# ProPrj_TK021F2699-RGB___24____2024-11-26.net
KiCad netlist of a schematic drawn in EasyEDA Pro
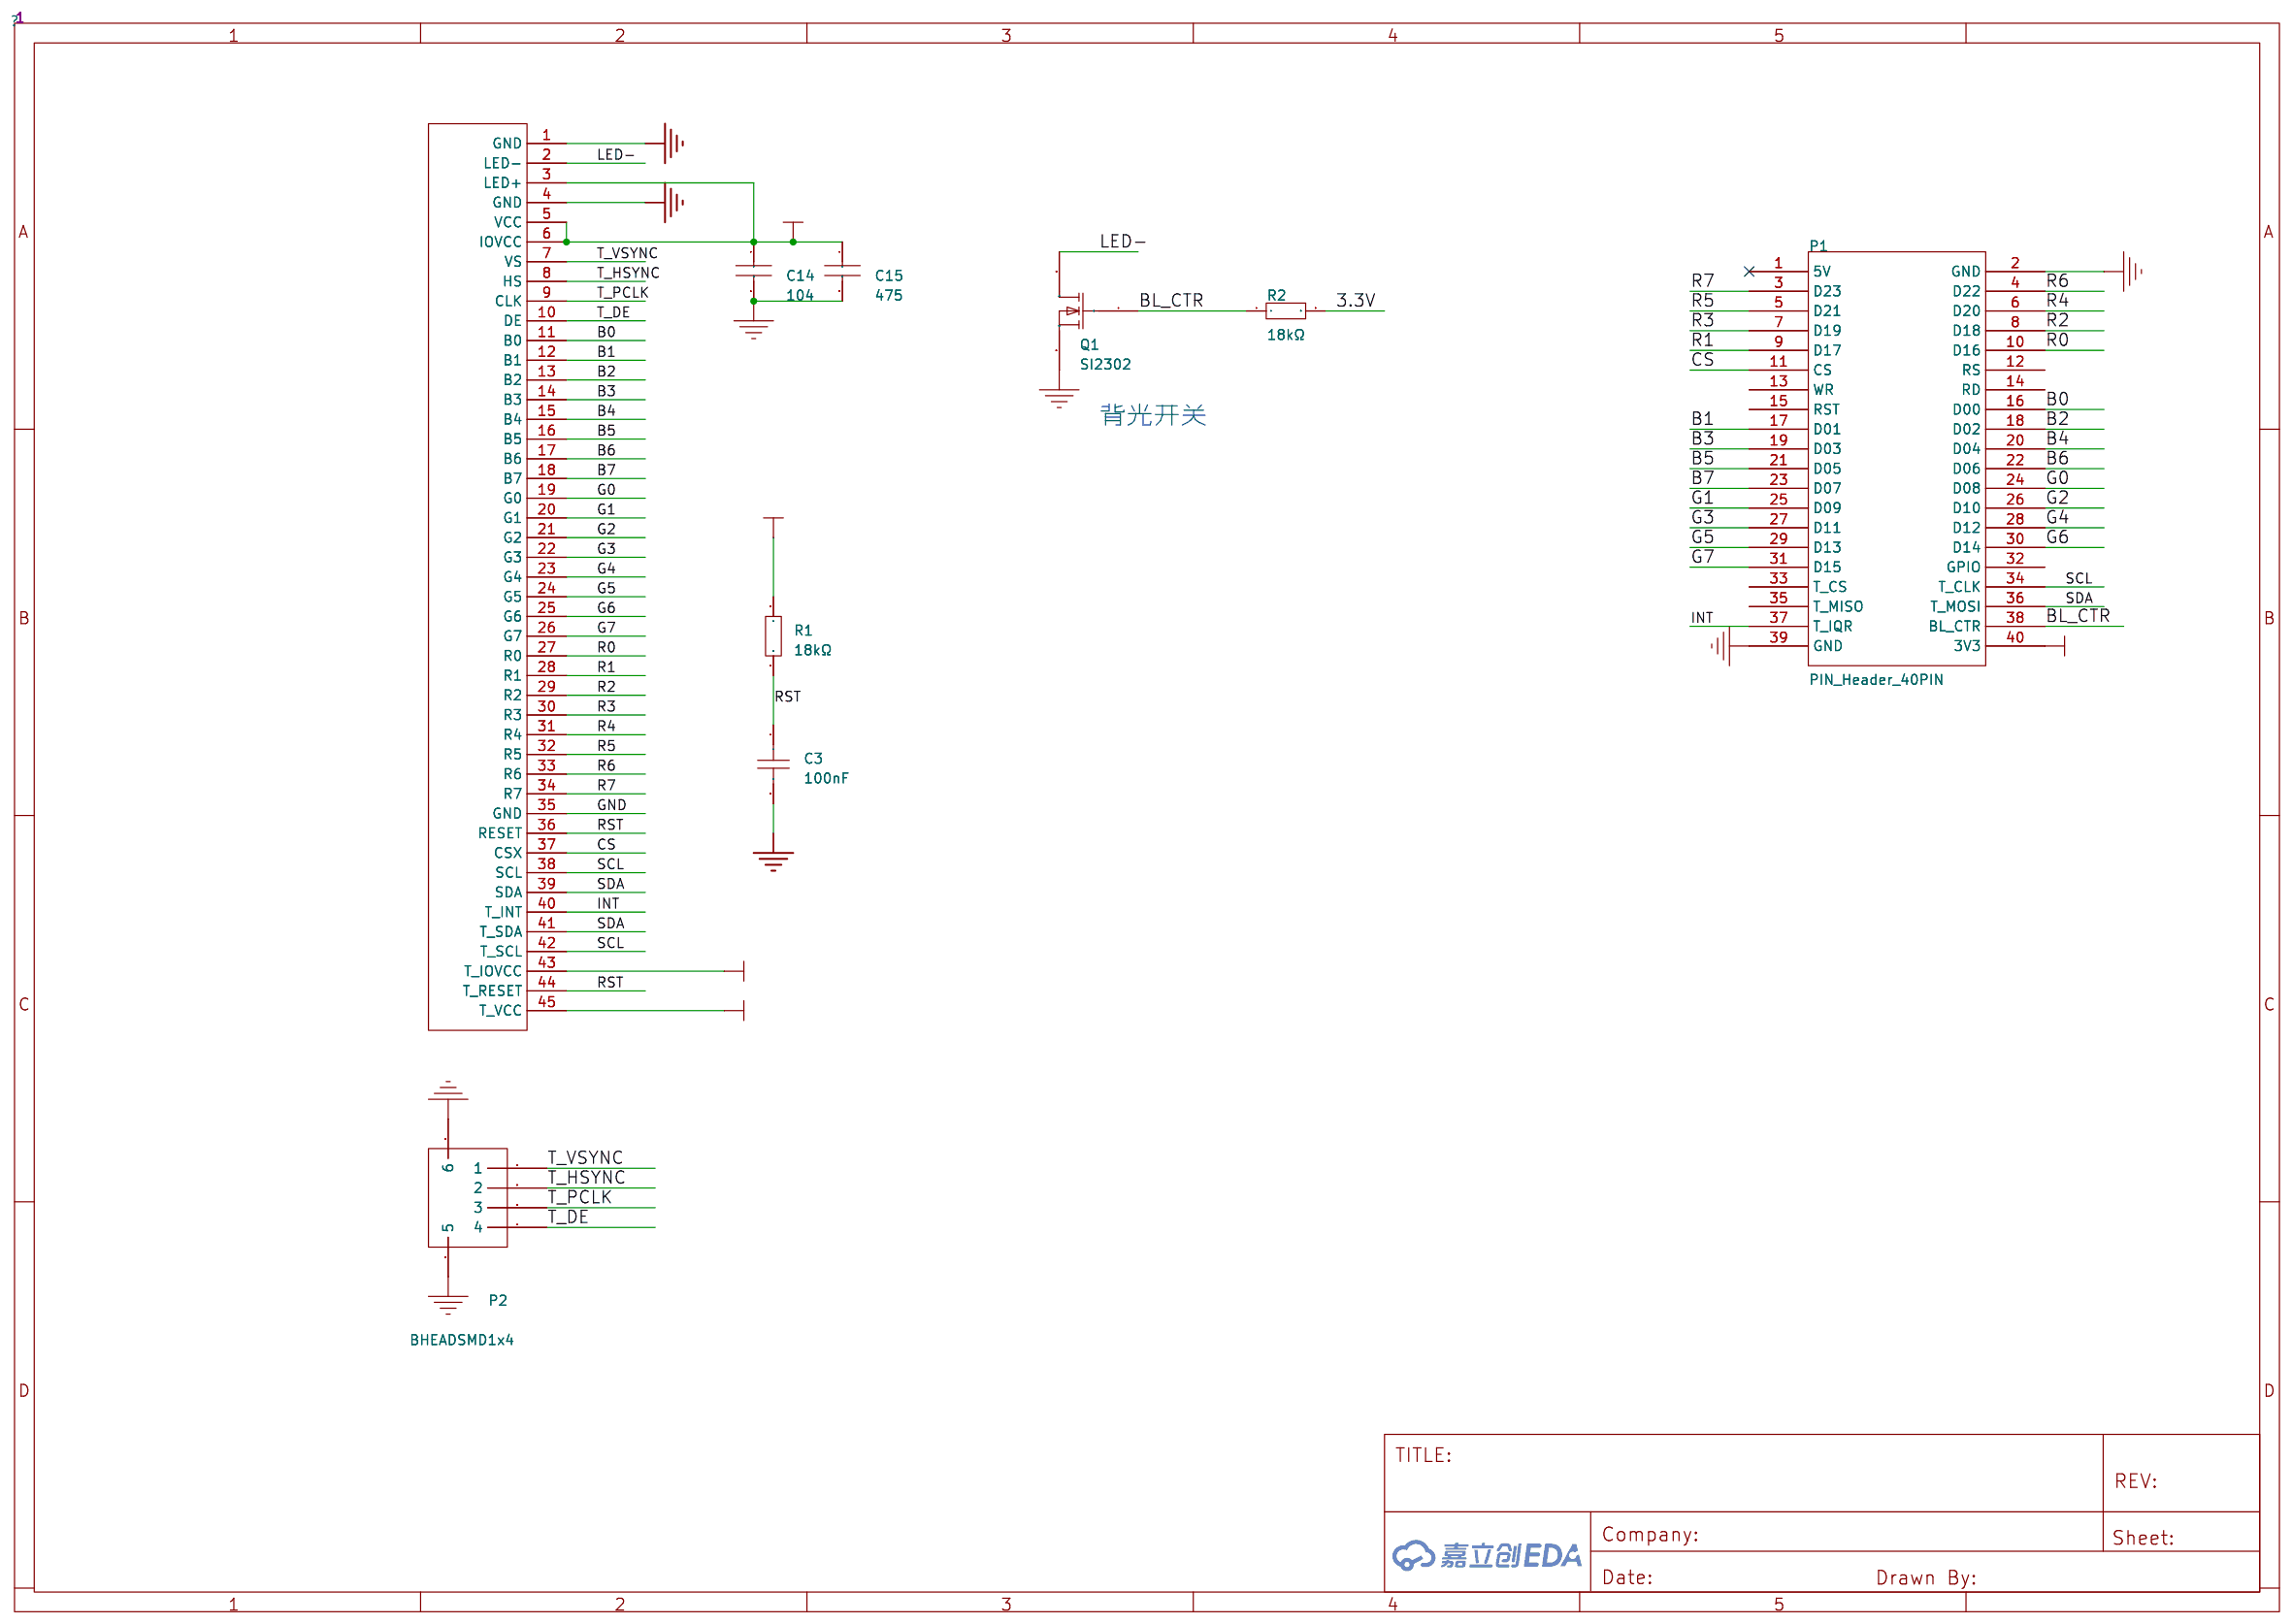
[diagram p0: schematic sheet]

(export (version "E")
  (design (tool "Eeschema 10.0.6"))
  (components
    (comp (ref "C3")
      (value "100nF")
      (footprint "easyedapro:C0603")
      (description "容值:100nF;精度:±10%;额定电压:50V;材质(温度系数):X7R;")
      (fields
        (field (name "Manufacturer Part") "CC0603KRX7R9BB104")
        (field (name "Manufacturer") "YAGEO(国巨)")
      )
      (libsource (lib "easyedapro") (part "CC0603KRX7R9BB104_1"))
    )
    (comp (ref "C14")
      (value "104")
      (footprint "easyedapro:C0603-1")
      (libsource (lib "easyedapro") (part "cap"))
    )
    (comp (ref "C15")
      (value "475")
      (footprint "easyedapro:C0603-1")
      (libsource (lib "easyedapro") (part "cap"))
    )
    (comp (ref "P1")
      (value "PIN_Header_40PIN")
      (footprint "easyedapro:P_Head_2x20")
      (libsource (lib "easyedapro") (part "PIN_Header_40PIN"))
    )
    (comp (ref "P2")
      (value "BHEADSMD1x4")
      (footprint "easyedapro:BHEADSMD1x4")
      (libsource (lib "easyedapro") (part "BHEADSMD1x4"))
    )
    (comp (ref "Q1")
      (value "SI2302")
      (footprint "easyedapro:SOT23A")
      (libsource (lib "easyedapro") (part "MOSFET-N"))
    )
    (comp (ref "R1")
      (value "18kΩ")
      (footprint "easyedapro:R0603")
      (description "电阻类型:厚膜电阻;阻值:18kΩ;精度:±1%;功率:100mW;最大工作电压:75V;温度系数:±100ppm/°C;")
      (fields
        (field (name "Manufacturer Part") "0603WAF1802T5E")
        (field (name "Manufacturer") "UNI-ROYAL(厚声)")
      )
      (libsource (lib "easyedapro") (part "0603WAF1802T5E_1"))
    )
    (comp (ref "R2")
      (value "18kΩ")
      (footprint "easyedapro:R0603")
      (description "电阻类型:厚膜电阻;阻值:18kΩ;精度:±1%;功率:100mW;最大工作电压:75V;温度系数:±100ppm/°C;")
      (fields
        (field (name "Manufacturer Part") "0603WAF1802T5E")
        (field (name "Manufacturer") "UNI-ROYAL(厚声)")
      )
      (libsource (lib "easyedapro") (part "0603WAF1802T5E_1"))
    )
    (comp (ref "U1")
      (value "~")
      (footprint "easyedapro:TK-45P")
      (libsource (lib "easyedapro") (part "TK021F2699-24"))
    )
  )
  (nets
    (net (code "1") (name "/B0") (class "Default")
      (node (ref "P1") (pin "16") (pinfunction "D00_16") (pintype "unspecified"))
      (node (ref "U1") (pin "11") (pinfunction "B0_11") (pintype "input"))
    )
    (net (code "2") (name "/B1") (class "Default")
      (node (ref "P1") (pin "17") (pinfunction "D01_17") (pintype "unspecified"))
      (node (ref "U1") (pin "12") (pinfunction "B1_12") (pintype "input"))
    )
    (net (code "3") (name "/B2") (class "Default")
      (node (ref "P1") (pin "18") (pinfunction "D02_18") (pintype "unspecified"))
      (node (ref "U1") (pin "13") (pinfunction "B2_13") (pintype "input"))
    )
    (net (code "4") (name "/B3") (class "Default")
      (node (ref "P1") (pin "19") (pinfunction "D03_19") (pintype "unspecified"))
      (node (ref "U1") (pin "14") (pinfunction "B3_14") (pintype "input"))
    )
    (net (code "5") (name "/B4") (class "Default")
      (node (ref "P1") (pin "20") (pinfunction "D04_20") (pintype "unspecified"))
      (node (ref "U1") (pin "15") (pinfunction "B4_15") (pintype "input"))
    )
    (net (code "6") (name "/B5") (class "Default")
      (node (ref "P1") (pin "21") (pinfunction "D05_21") (pintype "unspecified"))
      (node (ref "U1") (pin "16") (pinfunction "B5_16") (pintype "input"))
    )
    (net (code "7") (name "/B6") (class "Default")
      (node (ref "P1") (pin "22") (pinfunction "D06_22") (pintype "unspecified"))
      (node (ref "U1") (pin "17") (pinfunction "B6_17") (pintype "input"))
    )
    (net (code "8") (name "/B7") (class "Default")
      (node (ref "P1") (pin "23") (pinfunction "D07_23") (pintype "unspecified"))
      (node (ref "U1") (pin "18") (pinfunction "B7_18") (pintype "input"))
    )
    (net (code "9") (name "/BL_CTR") (class "Default")
      (node (ref "P1") (pin "38") (pinfunction "BL_CTR_38") (pintype "unspecified"))
      (node (ref "Q1") (pin "1") (pinfunction "G_1") (pintype "unspecified"))
      (node (ref "R2") (pin "1") (pinfunction "1_1") (pintype "input"))
    )
    (net (code "10") (name "/CS") (class "Default")
      (node (ref "P1") (pin "11") (pinfunction "CS_11") (pintype "unspecified"))
      (node (ref "U1") (pin "37") (pinfunction "CSX_37") (pintype "input"))
    )
    (net (code "11") (name "/G0") (class "Default")
      (node (ref "P1") (pin "24") (pinfunction "D08_24") (pintype "unspecified"))
      (node (ref "U1") (pin "19") (pinfunction "G0_19") (pintype "input"))
    )
    (net (code "12") (name "/G1") (class "Default")
      (node (ref "P1") (pin "25") (pinfunction "D09_25") (pintype "unspecified"))
      (node (ref "U1") (pin "20") (pinfunction "G1_20") (pintype "input"))
    )
    (net (code "13") (name "/G2") (class "Default")
      (node (ref "P1") (pin "26") (pinfunction "D10_26") (pintype "unspecified"))
      (node (ref "U1") (pin "21") (pinfunction "G2_21") (pintype "input"))
    )
    (net (code "14") (name "/G3") (class "Default")
      (node (ref "P1") (pin "27") (pinfunction "D11_27") (pintype "unspecified"))
      (node (ref "U1") (pin "22") (pinfunction "G3_22") (pintype "input"))
    )
    (net (code "15") (name "/G4") (class "Default")
      (node (ref "P1") (pin "28") (pinfunction "D12_28") (pintype "unspecified"))
      (node (ref "U1") (pin "23") (pinfunction "G4_23") (pintype "input"))
    )
    (net (code "16") (name "/G5") (class "Default")
      (node (ref "P1") (pin "29") (pinfunction "D13_29") (pintype "unspecified"))
      (node (ref "U1") (pin "24") (pinfunction "G5_24") (pintype "input"))
    )
    (net (code "17") (name "/G6") (class "Default")
      (node (ref "P1") (pin "30") (pinfunction "D14_30") (pintype "unspecified"))
      (node (ref "U1") (pin "25") (pinfunction "G6_25") (pintype "input"))
    )
    (net (code "18") (name "/G7") (class "Default")
      (node (ref "P1") (pin "31") (pinfunction "D15_31") (pintype "unspecified"))
      (node (ref "U1") (pin "26") (pinfunction "G7_26") (pintype "input"))
    )
    (net (code "19") (name "/INT") (class "Default")
      (node (ref "P1") (pin "37") (pinfunction "T_IQR_37") (pintype "unspecified"))
      (node (ref "U1") (pin "40") (pinfunction "T_INT_40") (pintype "input"))
    )
    (net (code "20") (name "/LED-") (class "Default")
      (node (ref "Q1") (pin "3") (pinfunction "D_3") (pintype "unspecified"))
      (node (ref "U1") (pin "2") (pinfunction "LED-_2") (pintype "input"))
    )
    (net (code "21") (name "/R0") (class "Default")
      (node (ref "P1") (pin "10") (pinfunction "D16_10") (pintype "unspecified"))
      (node (ref "U1") (pin "27") (pinfunction "R0_27") (pintype "input"))
    )
    (net (code "22") (name "/R1") (class "Default")
      (node (ref "P1") (pin "9") (pinfunction "D17_9") (pintype "unspecified"))
      (node (ref "U1") (pin "28") (pinfunction "R1_28") (pintype "input"))
    )
    (net (code "23") (name "/R2") (class "Default")
      (node (ref "P1") (pin "8") (pinfunction "D18_8") (pintype "unspecified"))
      (node (ref "U1") (pin "29") (pinfunction "R2_29") (pintype "input"))
    )
    (net (code "24") (name "/R3") (class "Default")
      (node (ref "P1") (pin "7") (pinfunction "D19_7") (pintype "unspecified"))
      (node (ref "U1") (pin "30") (pinfunction "R3_30") (pintype "input"))
    )
    (net (code "25") (name "/R4") (class "Default")
      (node (ref "P1") (pin "6") (pinfunction "D20_6") (pintype "unspecified"))
      (node (ref "U1") (pin "31") (pinfunction "R4_31") (pintype "input"))
    )
    (net (code "26") (name "/R5") (class "Default")
      (node (ref "P1") (pin "5") (pinfunction "D21_5") (pintype "unspecified"))
      (node (ref "U1") (pin "32") (pinfunction "R5_32") (pintype "input"))
    )
    (net (code "27") (name "/R6") (class "Default")
      (node (ref "P1") (pin "4") (pinfunction "D22_4") (pintype "unspecified"))
      (node (ref "U1") (pin "33") (pinfunction "R6_33") (pintype "input"))
    )
    (net (code "28") (name "/R7") (class "Default")
      (node (ref "P1") (pin "3") (pinfunction "D23_3") (pintype "unspecified"))
      (node (ref "U1") (pin "34") (pinfunction "R7_34") (pintype "input"))
    )
    (net (code "29") (name "/RST") (class "Default")
      (node (ref "C3") (pin "1") (pinfunction "1_1") (pintype "unspecified"))
      (node (ref "R1") (pin "1") (pinfunction "1_1") (pintype "input"))
      (node (ref "U1") (pin "36") (pinfunction "RESET_36") (pintype "input"))
      (node (ref "U1") (pin "44") (pinfunction "T_RESET_44") (pintype "input"))
    )
    (net (code "30") (name "/SCL") (class "Default")
      (node (ref "P1") (pin "34") (pinfunction "T_CLK_34") (pintype "unspecified"))
      (node (ref "U1") (pin "38") (pinfunction "SCL_38") (pintype "input"))
      (node (ref "U1") (pin "42") (pinfunction "T_SCL_42") (pintype "input"))
    )
    (net (code "31") (name "/SDA") (class "Default")
      (node (ref "P1") (pin "36") (pinfunction "T_MOSI_36") (pintype "unspecified"))
      (node (ref "U1") (pin "39") (pinfunction "SDA_39") (pintype "input"))
      (node (ref "U1") (pin "41") (pinfunction "T_SDA_41") (pintype "input"))
    )
    (net (code "32") (name "/T_DE") (class "Default")
      (node (ref "P2") (pin "4") (pinfunction "4_4") (pintype "unspecified"))
      (node (ref "U1") (pin "10") (pinfunction "DE_10") (pintype "input"))
    )
    (net (code "33") (name "/T_HSYNC") (class "Default")
      (node (ref "P2") (pin "2") (pinfunction "2_2") (pintype "unspecified"))
      (node (ref "U1") (pin "8") (pinfunction "HS_8") (pintype "input"))
    )
    (net (code "34") (name "/T_PCLK") (class "Default")
      (node (ref "P2") (pin "3") (pinfunction "3_3") (pintype "unspecified"))
      (node (ref "U1") (pin "9") (pinfunction "CLK_9") (pintype "input"))
    )
    (net (code "35") (name "/T_VSYNC") (class "Default")
      (node (ref "P2") (pin "1") (pinfunction "1_1") (pintype "unspecified"))
      (node (ref "U1") (pin "7") (pinfunction "VS_7") (pintype "input"))
    )
    (net (code "36") (name "3.3V") (class "Default")
      (node (ref "C14") (pin "1") (pinfunction "1_1") (pintype "unspecified"))
      (node (ref "C15") (pin "1") (pinfunction "1_1") (pintype "unspecified"))
      (node (ref "P1") (pin "40") (pinfunction "3V3_40") (pintype "unspecified"))
      (node (ref "R1") (pin "2") (pinfunction "2_2") (pintype "input"))
      (node (ref "R2") (pin "2") (pinfunction "2_2") (pintype "input"))
      (node (ref "U1") (pin "3") (pinfunction "LED+_3") (pintype "input"))
      (node (ref "U1") (pin "43") (pinfunction "T_IOVCC_43") (pintype "input"))
      (node (ref "U1") (pin "45") (pinfunction "T_VCC_45") (pintype "input"))
      (node (ref "U1") (pin "5") (pinfunction "VCC_5") (pintype "input"))
      (node (ref "U1") (pin "6") (pinfunction "IOVCC_6") (pintype "input"))
    )
    (net (code "37") (name "GND") (class "Default")
      (node (ref "C14") (pin "2") (pinfunction "2_2") (pintype "unspecified"))
      (node (ref "C15") (pin "2") (pinfunction "2_2") (pintype "unspecified"))
      (node (ref "C3") (pin "2") (pinfunction "2_2") (pintype "unspecified"))
      (node (ref "P1") (pin "2") (pinfunction "GND_2") (pintype "unspecified"))
      (node (ref "P1") (pin "39") (pinfunction "GND_39") (pintype "unspecified"))
      (node (ref "P2") (pin "5") (pinfunction "5_5") (pintype "unspecified"))
      (node (ref "P2") (pin "6") (pinfunction "6_6") (pintype "unspecified"))
      (node (ref "Q1") (pin "2") (pinfunction "S_2") (pintype "unspecified"))
      (node (ref "U1") (pin "1") (pinfunction "GND_1") (pintype "input"))
      (node (ref "U1") (pin "35") (pinfunction "GND_35") (pintype "input"))
      (node (ref "U1") (pin "4") (pinfunction "GND_4") (pintype "input"))
    )
    (net (code "38") (name "unconnected-(P1-5V-Pad1)") (class "Default")
      (node (ref "P1") (pin "1") (pinfunction "5V_1") (pintype "unspecified+no_connect"))
    )
    (net (code "39") (name "unconnected-(P1-GPIO-Pad32)") (class "Default")
      (node (ref "P1") (pin "32") (pinfunction "GPIO_32") (pintype "unspecified"))
    )
    (net (code "40") (name "unconnected-(P1-RD-Pad14)") (class "Default")
      (node (ref "P1") (pin "14") (pinfunction "RD_14") (pintype "unspecified"))
    )
    (net (code "41") (name "unconnected-(P1-RS-Pad12)") (class "Default")
      (node (ref "P1") (pin "12") (pinfunction "RS_12") (pintype "unspecified"))
    )
    (net (code "42") (name "unconnected-(P1-RST-Pad15)") (class "Default")
      (node (ref "P1") (pin "15") (pinfunction "RST_15") (pintype "unspecified"))
    )
    (net (code "43") (name "unconnected-(P1-T_CS-Pad33)") (class "Default")
      (node (ref "P1") (pin "33") (pinfunction "T_CS_33") (pintype "unspecified"))
    )
    (net (code "44") (name "unconnected-(P1-T_MISO-Pad35)") (class "Default")
      (node (ref "P1") (pin "35") (pinfunction "T_MISO_35") (pintype "unspecified"))
    )
    (net (code "45") (name "unconnected-(P1-WR-Pad13)") (class "Default")
      (node (ref "P1") (pin "13") (pinfunction "WR_13") (pintype "unspecified"))
    )
  )
)
